# SIDEPANEL3_1.net
KiCad netlist of a schematic drawn in EAGLE
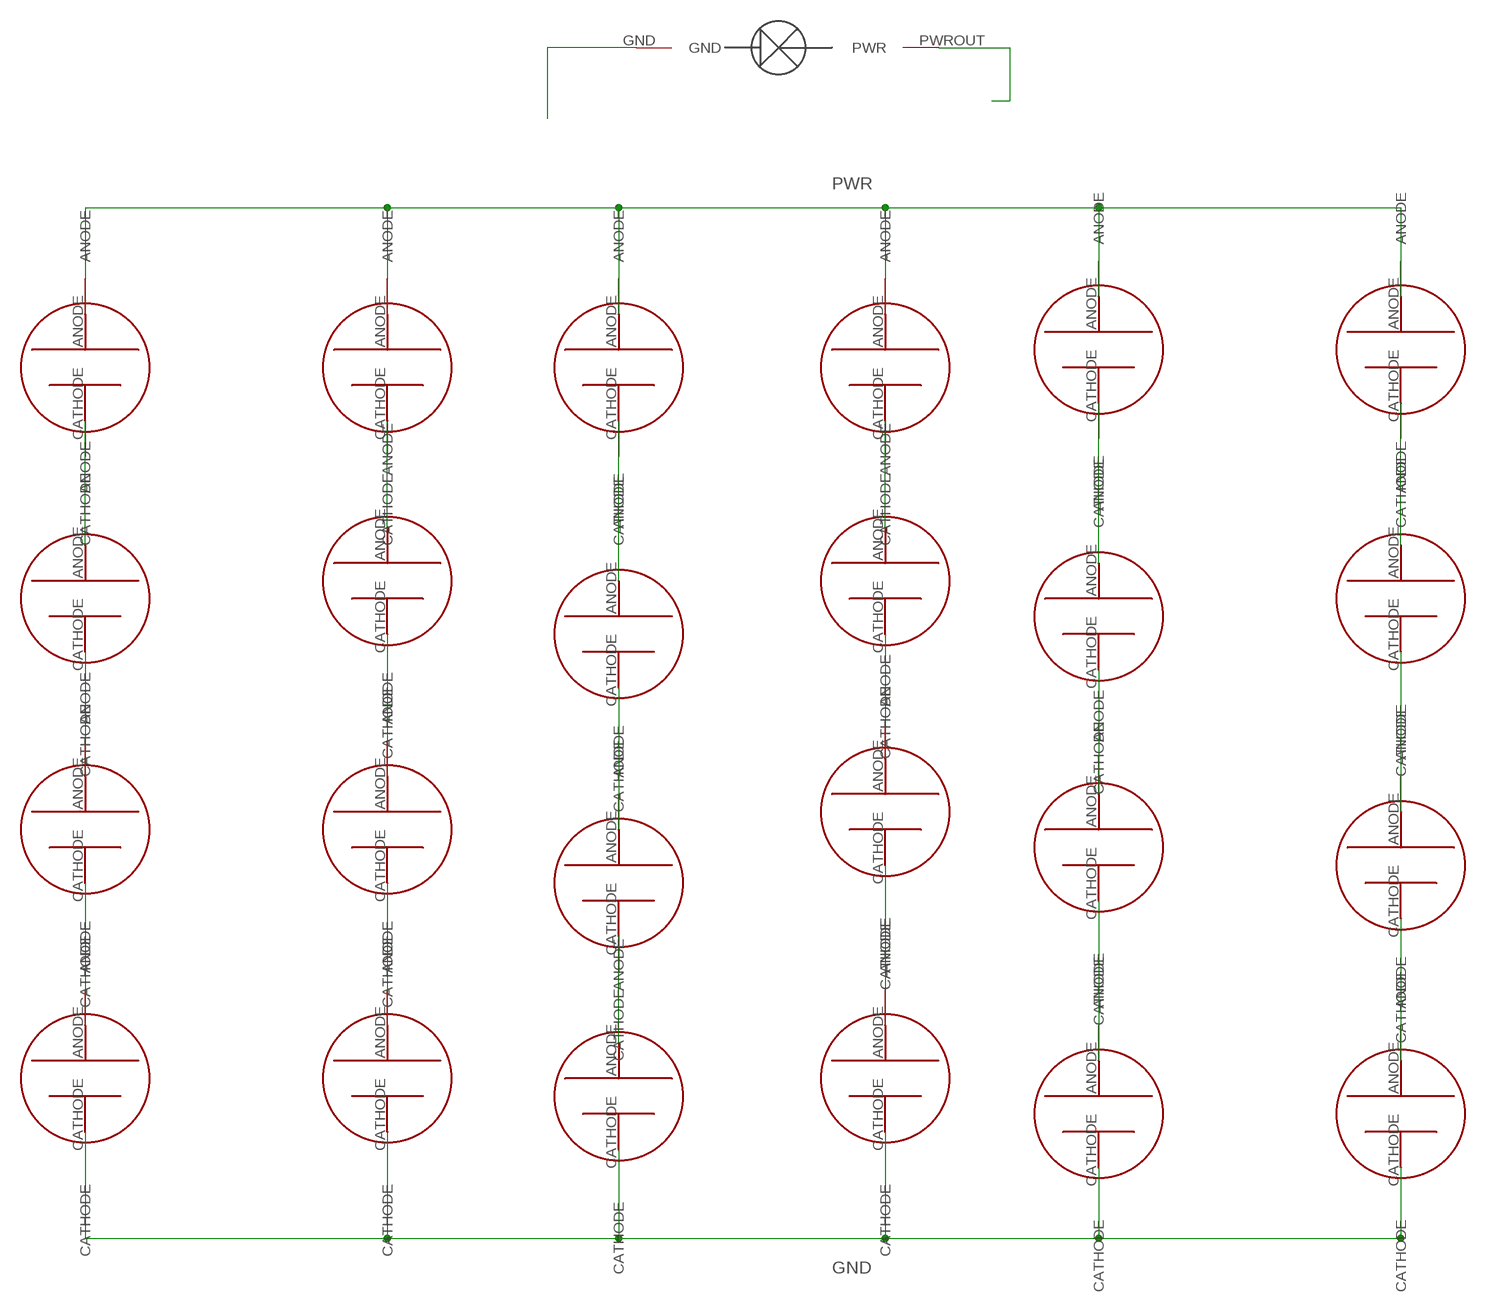
[diagram p0: schematic, sheet 1]

(export (version "E")
  (design (tool "Eeschema 10.0.6"))
  (components
    (comp (ref "1A")
      (value "NEWSOLARPANEL")
      (footprint "eagle-import:SOLARCELL2")
      (libsource (lib "eagle-import") (part "NEWSOLARPANEL"))
    )
    (comp (ref "1B")
      (value "NEWSOLARPANEL")
      (footprint "eagle-import:SOLARCELL2")
      (libsource (lib "eagle-import") (part "NEWSOLARPANEL"))
    )
    (comp (ref "1C")
      (value "NEWSOLARPANEL")
      (footprint "eagle-import:SOLARCELL2")
      (libsource (lib "eagle-import") (part "NEWSOLARPANEL"))
    )
    (comp (ref "1D")
      (value "NEWSOLARPANEL")
      (footprint "eagle-import:SOLARCELL2")
      (libsource (lib "eagle-import") (part "NEWSOLARPANEL"))
    )
    (comp (ref "1F")
      (value "NEWSOLARPANEL")
      (footprint "eagle-import:SOLARCELL2")
      (libsource (lib "eagle-import") (part "NEWSOLARPANEL"))
    )
    (comp (ref "1G")
      (value "NEWSOLARPANEL")
      (footprint "eagle-import:SOLARCELL2")
      (libsource (lib "eagle-import") (part "NEWSOLARPANEL"))
    )
    (comp (ref "2A")
      (value "NEWSOLARPANEL")
      (footprint "eagle-import:SOLARCELL2")
      (libsource (lib "eagle-import") (part "NEWSOLARPANEL"))
    )
    (comp (ref "2B")
      (value "NEWSOLARPANEL")
      (footprint "eagle-import:SOLARCELL2")
      (libsource (lib "eagle-import") (part "NEWSOLARPANEL"))
    )
    (comp (ref "2C")
      (value "NEWSOLARPANEL")
      (footprint "eagle-import:SOLARCELL2")
      (libsource (lib "eagle-import") (part "NEWSOLARPANEL"))
    )
    (comp (ref "2D")
      (value "NEWSOLARPANEL")
      (footprint "eagle-import:SOLARCELL2")
      (libsource (lib "eagle-import") (part "NEWSOLARPANEL"))
    )
    (comp (ref "2F")
      (value "NEWSOLARPANEL")
      (footprint "eagle-import:SOLARCELL2")
      (libsource (lib "eagle-import") (part "NEWSOLARPANEL"))
    )
    (comp (ref "2G")
      (value "NEWSOLARPANEL")
      (footprint "eagle-import:SOLARCELL2")
      (libsource (lib "eagle-import") (part "NEWSOLARPANEL"))
    )
    (comp (ref "3A")
      (value "NEWSOLARPANEL")
      (footprint "eagle-import:SOLARCELL2")
      (libsource (lib "eagle-import") (part "NEWSOLARPANEL"))
    )
    (comp (ref "3B")
      (value "NEWSOLARPANEL")
      (footprint "eagle-import:SOLARCELL2")
      (libsource (lib "eagle-import") (part "NEWSOLARPANEL"))
    )
    (comp (ref "3C")
      (value "NEWSOLARPANEL")
      (footprint "eagle-import:SOLARCELL2")
      (libsource (lib "eagle-import") (part "NEWSOLARPANEL"))
    )
    (comp (ref "3D")
      (value "NEWSOLARPANEL")
      (footprint "eagle-import:SOLARCELL2")
      (libsource (lib "eagle-import") (part "NEWSOLARPANEL"))
    )
    (comp (ref "3F")
      (value "NEWSOLARPANEL")
      (footprint "eagle-import:SOLARCELL2")
      (libsource (lib "eagle-import") (part "NEWSOLARPANEL"))
    )
    (comp (ref "3G")
      (value "NEWSOLARPANEL")
      (footprint "eagle-import:SOLARCELL2")
      (libsource (lib "eagle-import") (part "NEWSOLARPANEL"))
    )
    (comp (ref "4A")
      (value "NEWSOLARPANEL")
      (footprint "eagle-import:SOLARCELL2")
      (libsource (lib "eagle-import") (part "NEWSOLARPANEL"))
    )
    (comp (ref "4B")
      (value "NEWSOLARPANEL")
      (footprint "eagle-import:SOLARCELL2")
      (libsource (lib "eagle-import") (part "NEWSOLARPANEL"))
    )
    (comp (ref "4C")
      (value "NEWSOLARPANEL")
      (footprint "eagle-import:SOLARCELL2")
      (libsource (lib "eagle-import") (part "NEWSOLARPANEL"))
    )
    (comp (ref "4D")
      (value "NEWSOLARPANEL")
      (footprint "eagle-import:SOLARCELL2")
      (libsource (lib "eagle-import") (part "NEWSOLARPANEL"))
    )
    (comp (ref "4F")
      (value "NEWSOLARPANEL")
      (footprint "eagle-import:SOLARCELL2")
      (libsource (lib "eagle-import") (part "NEWSOLARPANEL"))
    )
    (comp (ref "4G")
      (value "NEWSOLARPANEL")
      (footprint "eagle-import:SOLARCELL2")
      (libsource (lib "eagle-import") (part "NEWSOLARPANEL"))
    )
    (comp (ref "U$1")
      (value "PHOTODETECTOR")
      (footprint "eagle-import:PHOTODECTORDEVICE2")
      (libsource (lib "eagle-import") (part "PHOTODETECTOR"))
    )
  )
  (nets
    (net (code "1") (name "/GND") (class "Default")
      (node (ref "4A") (pin "CATHODE") (pinfunction "CATHODE_CATHODE") (pintype "bidirectional"))
      (node (ref "4B") (pin "CATHODE") (pinfunction "CATHODE_CATHODE") (pintype "bidirectional"))
      (node (ref "4C") (pin "CATHODE") (pinfunction "CATHODE_CATHODE") (pintype "bidirectional"))
      (node (ref "4D") (pin "CATHODE") (pinfunction "CATHODE_CATHODE") (pintype "bidirectional"))
      (node (ref "4F") (pin "CATHODE") (pinfunction "CATHODE_CATHODE") (pintype "bidirectional"))
      (node (ref "4G") (pin "CATHODE") (pinfunction "CATHODE_CATHODE") (pintype "bidirectional"))
      (node (ref "U$1") (pin "GND") (pinfunction "GND_GND") (pintype "bidirectional"))
    )
    (net (code "2") (name "/PWR") (class "Default")
      (node (ref "1A") (pin "ANODE") (pinfunction "ANODE_ANODE") (pintype "bidirectional"))
      (node (ref "1B") (pin "ANODE") (pinfunction "ANODE_ANODE") (pintype "bidirectional"))
      (node (ref "1C") (pin "ANODE") (pinfunction "ANODE_ANODE") (pintype "bidirectional"))
      (node (ref "1D") (pin "ANODE") (pinfunction "ANODE_ANODE") (pintype "bidirectional"))
      (node (ref "1F") (pin "ANODE") (pinfunction "ANODE_ANODE") (pintype "bidirectional"))
      (node (ref "1G") (pin "ANODE") (pinfunction "ANODE_ANODE") (pintype "bidirectional"))
    )
    (net (code "3") (name "Net-(1A-PadCATHODE)") (class "Default")
      (node (ref "1A") (pin "CATHODE") (pinfunction "CATHODE_CATHODE") (pintype "bidirectional"))
      (node (ref "2A") (pin "ANODE") (pinfunction "ANODE_ANODE") (pintype "bidirectional"))
    )
    (net (code "4") (name "Net-(1B-PadCATHODE)") (class "Default")
      (node (ref "1B") (pin "CATHODE") (pinfunction "CATHODE_CATHODE") (pintype "bidirectional"))
      (node (ref "2B") (pin "ANODE") (pinfunction "ANODE_ANODE") (pintype "bidirectional"))
    )
    (net (code "5") (name "Net-(1C-PadCATHODE)") (class "Default")
      (node (ref "1C") (pin "CATHODE") (pinfunction "CATHODE_CATHODE") (pintype "bidirectional"))
      (node (ref "2C") (pin "ANODE") (pinfunction "ANODE_ANODE") (pintype "bidirectional"))
    )
    (net (code "6") (name "Net-(1D-PadCATHODE)") (class "Default")
      (node (ref "1D") (pin "CATHODE") (pinfunction "CATHODE_CATHODE") (pintype "bidirectional"))
      (node (ref "2D") (pin "ANODE") (pinfunction "ANODE_ANODE") (pintype "bidirectional"))
    )
    (net (code "7") (name "Net-(1F-PadCATHODE)") (class "Default")
      (node (ref "1F") (pin "CATHODE") (pinfunction "CATHODE_CATHODE") (pintype "bidirectional"))
      (node (ref "2F") (pin "ANODE") (pinfunction "ANODE_ANODE") (pintype "bidirectional"))
    )
    (net (code "8") (name "Net-(1G-PadCATHODE)") (class "Default")
      (node (ref "1G") (pin "CATHODE") (pinfunction "CATHODE_CATHODE") (pintype "bidirectional"))
      (node (ref "2G") (pin "ANODE") (pinfunction "ANODE_ANODE") (pintype "bidirectional"))
    )
    (net (code "9") (name "Net-(2A-PadCATHODE)") (class "Default")
      (node (ref "2A") (pin "CATHODE") (pinfunction "CATHODE_CATHODE") (pintype "bidirectional"))
      (node (ref "3A") (pin "ANODE") (pinfunction "ANODE_ANODE") (pintype "bidirectional"))
    )
    (net (code "10") (name "Net-(2B-PadCATHODE)") (class "Default")
      (node (ref "2B") (pin "CATHODE") (pinfunction "CATHODE_CATHODE") (pintype "bidirectional"))
      (node (ref "3B") (pin "ANODE") (pinfunction "ANODE_ANODE") (pintype "bidirectional"))
    )
    (net (code "11") (name "Net-(2C-PadCATHODE)") (class "Default")
      (node (ref "2C") (pin "CATHODE") (pinfunction "CATHODE_CATHODE") (pintype "bidirectional"))
      (node (ref "3C") (pin "ANODE") (pinfunction "ANODE_ANODE") (pintype "bidirectional"))
    )
    (net (code "12") (name "Net-(2D-PadCATHODE)") (class "Default")
      (node (ref "2D") (pin "CATHODE") (pinfunction "CATHODE_CATHODE") (pintype "bidirectional"))
      (node (ref "3D") (pin "ANODE") (pinfunction "ANODE_ANODE") (pintype "bidirectional"))
    )
    (net (code "13") (name "Net-(2F-PadCATHODE)") (class "Default")
      (node (ref "2F") (pin "CATHODE") (pinfunction "CATHODE_CATHODE") (pintype "bidirectional"))
      (node (ref "3F") (pin "ANODE") (pinfunction "ANODE_ANODE") (pintype "bidirectional"))
    )
    (net (code "14") (name "Net-(2G-PadCATHODE)") (class "Default")
      (node (ref "2G") (pin "CATHODE") (pinfunction "CATHODE_CATHODE") (pintype "bidirectional"))
      (node (ref "3G") (pin "ANODE") (pinfunction "ANODE_ANODE") (pintype "bidirectional"))
    )
    (net (code "15") (name "Net-(3A-PadCATHODE)") (class "Default")
      (node (ref "3A") (pin "CATHODE") (pinfunction "CATHODE_CATHODE") (pintype "bidirectional"))
      (node (ref "4A") (pin "ANODE") (pinfunction "ANODE_ANODE") (pintype "bidirectional"))
    )
    (net (code "16") (name "Net-(3B-PadCATHODE)") (class "Default")
      (node (ref "3B") (pin "CATHODE") (pinfunction "CATHODE_CATHODE") (pintype "bidirectional"))
      (node (ref "4B") (pin "ANODE") (pinfunction "ANODE_ANODE") (pintype "bidirectional"))
    )
    (net (code "17") (name "Net-(3C-PadCATHODE)") (class "Default")
      (node (ref "3C") (pin "CATHODE") (pinfunction "CATHODE_CATHODE") (pintype "bidirectional"))
      (node (ref "4C") (pin "ANODE") (pinfunction "ANODE_ANODE") (pintype "bidirectional"))
    )
    (net (code "18") (name "Net-(3D-PadCATHODE)") (class "Default")
      (node (ref "3D") (pin "CATHODE") (pinfunction "CATHODE_CATHODE") (pintype "bidirectional"))
      (node (ref "4D") (pin "ANODE") (pinfunction "ANODE_ANODE") (pintype "bidirectional"))
    )
    (net (code "19") (name "Net-(3F-PadCATHODE)") (class "Default")
      (node (ref "3F") (pin "CATHODE") (pinfunction "CATHODE_CATHODE") (pintype "bidirectional"))
      (node (ref "4F") (pin "ANODE") (pinfunction "ANODE_ANODE") (pintype "bidirectional"))
    )
    (net (code "20") (name "Net-(3G-PadCATHODE)") (class "Default")
      (node (ref "3G") (pin "CATHODE") (pinfunction "CATHODE_CATHODE") (pintype "bidirectional"))
      (node (ref "4G") (pin "ANODE") (pinfunction "ANODE_ANODE") (pintype "bidirectional"))
    )
    (net (code "21") (name "unconnected-(U$1-PWR-PadPWROUT)") (class "Default")
      (node (ref "U$1") (pin "PWROUT") (pinfunction "PWR_PWROUT") (pintype "bidirectional"))
    )
  )
)
